# Asistente_Alzhaimer.net
KiCad netlist of a schematic drawn in EAGLE
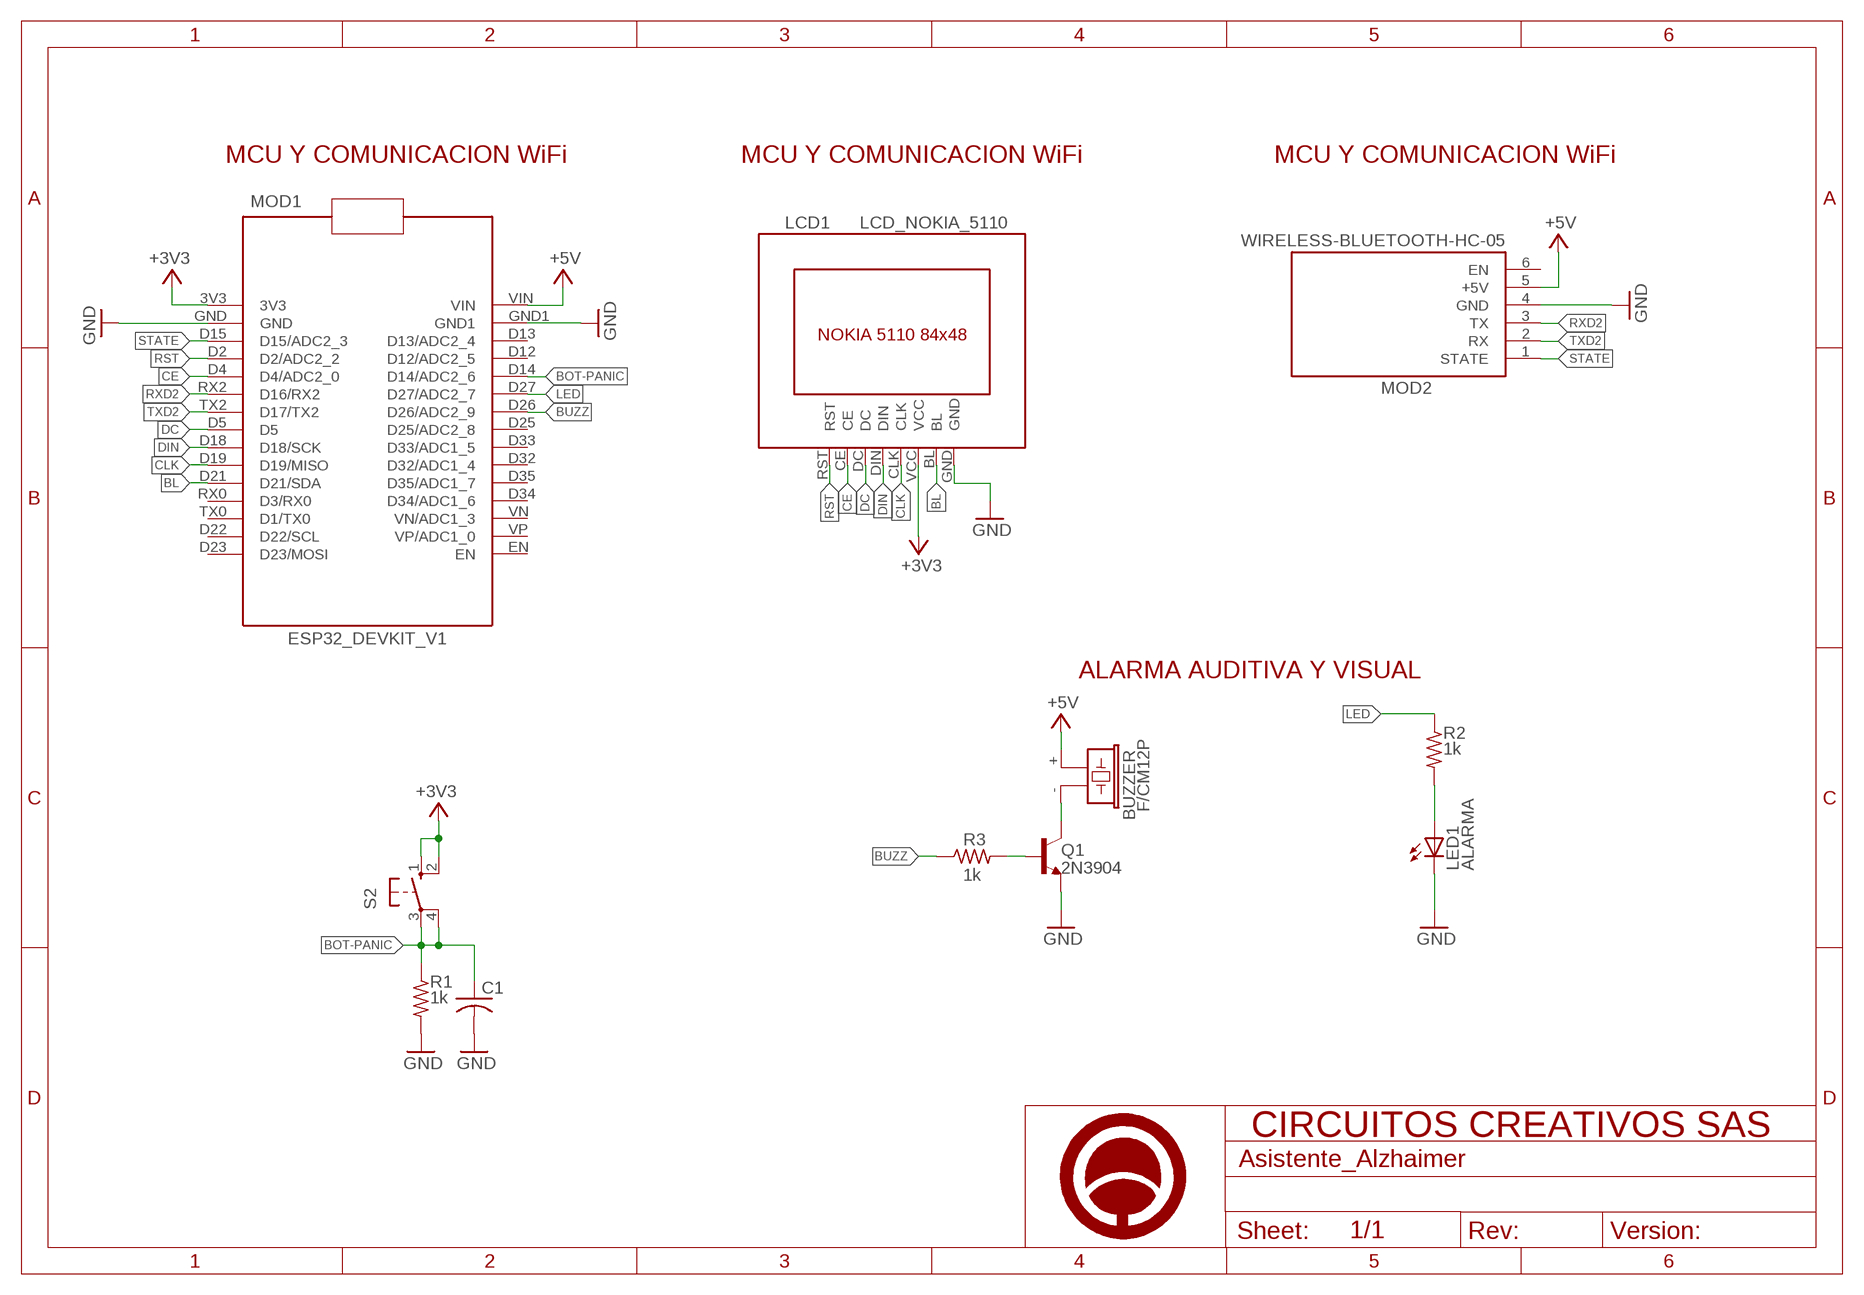
[diagram p0: schematic, sheet 1]

(export (version "E")
  (design (tool "Eeschema 10.0.6"))
  (components
    (comp (ref "BUZZER")
      (value "F/CM12P")
      (footprint "eagle-import:F_CM12P")
      (libsource (lib "eagle-import") (part "F/CM12P"))
    )
    (comp (ref "C1")
      (value "C-US050-025X075")
      (footprint "eagle-import:C050-025X075")
      (libsource (lib "eagle-import") (part "C-US050-025X075"))
    )
    (comp (ref "LCD1")
      (value "LCD_NOKIA_5110")
      (footprint "eagle-import:NOKIA_5110_THT")
      (libsource (lib "eagle-import") (part "LCD_NOKIA_5110"))
    )
    (comp (ref "LED1")
      (value "ALARMA")
      (footprint "eagle-import:LED3MM")
      (libsource (lib "eagle-import") (part "LED3MM"))
    )
    (comp (ref "MOD1")
      (value "ESP32_DEVKIT_V1")
      (footprint "eagle-import:ESP32_DEVKIT_V1")
      (libsource (lib "eagle-import") (part "ESP32_DEVKIT_V1"))
    )
    (comp (ref "MOD2")
      (value "WIRELESS-BLUETOOTH-HC-05")
      (footprint "eagle-import:WIRELESS-BLUETOOTH-HC-05")
      (libsource (lib "eagle-import") (part "WIRELESS-BLUETOOTH-HC-05"))
    )
    (comp (ref "Q1")
      (value "2N3904")
      (footprint "eagle-import:TO-92")
      (libsource (lib "eagle-import") (part "2N3904"))
    )
    (comp (ref "R1")
      (value "1k")
      (footprint "eagle-import:0204_7")
      (libsource (lib "eagle-import") (part "R-US_0204/7"))
    )
    (comp (ref "R2")
      (value "1k")
      (footprint "eagle-import:0204_7")
      (libsource (lib "eagle-import") (part "R-US_0204/7"))
    )
    (comp (ref "R3")
      (value "1k")
      (footprint "eagle-import:0204_7")
      (libsource (lib "eagle-import") (part "R-US_0204/7"))
    )
    (comp (ref "S2")
      (value "10-XX")
      (footprint "eagle-import:B3F-10XX")
      (fields (field (name "MPN") "B3F-1000"))
      (libsource (lib "eagle-import") (part "10-XX"))
    )
    (comp (ref "U$1")
      (value "A4_HORIZONTAL")
      (footprint "eagle-import:LOGO")
      (libsource (lib "eagle-import") (part "A4_HORIZONTAL"))
    )
  )
  (nets
    (net (code "1") (name "+3V3") (class "Default")
      (node (ref "LCD1") (pin "VCC") (pinfunction "VCC_VCC") (pintype "power_in"))
      (node (ref "MOD1") (pin "3V3") (pinfunction "3V3_3V3") (pintype "power_in"))
      (node (ref "S2") (pin "1") (pinfunction "S_1") (pintype "passive"))
      (node (ref "S2") (pin "2") (pinfunction "S1_2") (pintype "passive"))
    )
    (net (code "2") (name "+5V") (class "Default")
      (node (ref "BUZZER") (pin "+") (pinfunction "1_+") (pintype "passive"))
      (node (ref "MOD1") (pin "VIN") (pinfunction "VIN_VIN") (pintype "power_in"))
      (node (ref "MOD2") (pin "5") (pinfunction "+5V_5") (pintype "power_in"))
    )
    (net (code "3") (name "BL") (class "Default")
      (node (ref "LCD1") (pin "BL") (pinfunction "BL_BL") (pintype "bidirectional"))
      (node (ref "MOD1") (pin "D21") (pinfunction "D21/SDA_D21") (pintype "bidirectional"))
    )
    (net (code "4") (name "BOT-PANIC") (class "Default")
      (node (ref "C1") (pin "1") (pinfunction "1_1") (pintype "passive"))
      (node (ref "MOD1") (pin "D14") (pinfunction "D14/ADC2_6_D14") (pintype "bidirectional"))
      (node (ref "R1") (pin "1") (pinfunction "1_1") (pintype "passive"))
      (node (ref "S2") (pin "3") (pinfunction "P_3") (pintype "passive"))
      (node (ref "S2") (pin "4") (pinfunction "P1_4") (pintype "passive"))
    )
    (net (code "5") (name "BUZZ") (class "Default")
      (node (ref "MOD1") (pin "D26") (pinfunction "D26/ADC2_9_D26") (pintype "bidirectional"))
      (node (ref "R3") (pin "1") (pinfunction "1_1") (pintype "passive"))
    )
    (net (code "6") (name "CE") (class "Default")
      (node (ref "LCD1") (pin "CE") (pinfunction "CE_CE") (pintype "bidirectional"))
      (node (ref "MOD1") (pin "D4") (pinfunction "D4/ADC2_0_D4") (pintype "bidirectional"))
    )
    (net (code "7") (name "CLK") (class "Default")
      (node (ref "LCD1") (pin "CLK") (pinfunction "CLK_CLK") (pintype "bidirectional"))
      (node (ref "MOD1") (pin "D19") (pinfunction "D19/MISO_D19") (pintype "bidirectional"))
    )
    (net (code "8") (name "DC") (class "Default")
      (node (ref "LCD1") (pin "DC") (pinfunction "DC_DC") (pintype "bidirectional"))
      (node (ref "MOD1") (pin "D5") (pinfunction "D5_D5") (pintype "bidirectional"))
    )
    (net (code "9") (name "DIN") (class "Default")
      (node (ref "LCD1") (pin "DIN") (pinfunction "DIN_DIN") (pintype "bidirectional"))
      (node (ref "MOD1") (pin "D18") (pinfunction "D18/SCK_D18") (pintype "bidirectional"))
    )
    (net (code "10") (name "GND") (class "Default")
      (node (ref "C1") (pin "2") (pinfunction "2_2") (pintype "passive"))
      (node (ref "LCD1") (pin "GND") (pinfunction "GND_GND") (pintype "power_in"))
      (node (ref "LED1") (pin "K") (pinfunction "C_K") (pintype "passive"))
      (node (ref "MOD1") (pin "GND") (pinfunction "GND_GND") (pintype "power_in"))
      (node (ref "MOD1") (pin "GND1") (pinfunction "GND1_GND1") (pintype "power_in"))
      (node (ref "MOD2") (pin "4") (pinfunction "GND_4") (pintype "power_in"))
      (node (ref "Q1") (pin "1") (pinfunction "E_1") (pintype "passive"))
      (node (ref "R1") (pin "2") (pinfunction "2_2") (pintype "passive"))
    )
    (net (code "11") (name "LED") (class "Default")
      (node (ref "MOD1") (pin "D27") (pinfunction "D27/ADC2_7_D27") (pintype "bidirectional"))
      (node (ref "R2") (pin "1") (pinfunction "1_1") (pintype "passive"))
    )
    (net (code "12") (name "Net-(BUZZER-2)") (class "Default")
      (node (ref "BUZZER") (pin "-") (pinfunction "2_-") (pintype "passive"))
      (node (ref "Q1") (pin "3") (pinfunction "C_3") (pintype "passive"))
    )
    (net (code "13") (name "Net-(LED1-PadA)") (class "Default")
      (node (ref "LED1") (pin "A") (pinfunction "A_A") (pintype "passive"))
      (node (ref "R2") (pin "2") (pinfunction "2_2") (pintype "passive"))
    )
    (net (code "14") (name "Net-(Q1-B)") (class "Default")
      (node (ref "Q1") (pin "2") (pinfunction "B_2") (pintype "passive"))
      (node (ref "R3") (pin "2") (pinfunction "2_2") (pintype "passive"))
    )
    (net (code "15") (name "RST") (class "Default")
      (node (ref "LCD1") (pin "RST") (pinfunction "RST_RST") (pintype "bidirectional"))
      (node (ref "MOD1") (pin "D2") (pinfunction "D2/ADC2_2_D2") (pintype "bidirectional"))
    )
    (net (code "16") (name "RXD2") (class "Default")
      (node (ref "MOD1") (pin "RX2") (pinfunction "D16/RX2_RX2") (pintype "bidirectional"))
      (node (ref "MOD2") (pin "3") (pinfunction "TX_3") (pintype "bidirectional"))
    )
    (net (code "17") (name "STATE") (class "Default")
      (node (ref "MOD1") (pin "D15") (pinfunction "D15/ADC2_3_D15") (pintype "bidirectional"))
      (node (ref "MOD2") (pin "1") (pinfunction "STATE_1") (pintype "bidirectional"))
    )
    (net (code "18") (name "TXD2") (class "Default")
      (node (ref "MOD1") (pin "TX2") (pinfunction "D17/TX2_TX2") (pintype "bidirectional"))
      (node (ref "MOD2") (pin "2") (pinfunction "RX_2") (pintype "bidirectional"))
    )
    (net (code "19") (name "unconnected-(MOD1-D1{slash}TX0-PadTX0)") (class "Default")
      (node (ref "MOD1") (pin "TX0") (pinfunction "D1/TX0_TX0") (pintype "bidirectional"))
    )
    (net (code "20") (name "unconnected-(MOD1-D3{slash}RX0-PadRX0)") (class "Default")
      (node (ref "MOD1") (pin "RX0") (pinfunction "D3/RX0_RX0") (pintype "bidirectional"))
    )
    (net (code "21") (name "unconnected-(MOD1-D12{slash}ADC2_5-PadD12)") (class "Default")
      (node (ref "MOD1") (pin "D12") (pinfunction "D12/ADC2_5_D12") (pintype "bidirectional"))
    )
    (net (code "22") (name "unconnected-(MOD1-D13{slash}ADC2_4-PadD13)") (class "Default")
      (node (ref "MOD1") (pin "D13") (pinfunction "D13/ADC2_4_D13") (pintype "bidirectional"))
    )
    (net (code "23") (name "unconnected-(MOD1-D22{slash}SCL-PadD22)") (class "Default")
      (node (ref "MOD1") (pin "D22") (pinfunction "D22/SCL_D22") (pintype "bidirectional"))
    )
    (net (code "24") (name "unconnected-(MOD1-D23{slash}MOSI-PadD23)") (class "Default")
      (node (ref "MOD1") (pin "D23") (pinfunction "D23/MOSI_D23") (pintype "bidirectional"))
    )
    (net (code "25") (name "unconnected-(MOD1-D25{slash}ADC2_8-PadD25)") (class "Default")
      (node (ref "MOD1") (pin "D25") (pinfunction "D25/ADC2_8_D25") (pintype "bidirectional"))
    )
    (net (code "26") (name "unconnected-(MOD1-D32{slash}ADC1_4-PadD32)") (class "Default")
      (node (ref "MOD1") (pin "D32") (pinfunction "D32/ADC1_4_D32") (pintype "bidirectional"))
    )
    (net (code "27") (name "unconnected-(MOD1-D33{slash}ADC1_5-PadD33)") (class "Default")
      (node (ref "MOD1") (pin "D33") (pinfunction "D33/ADC1_5_D33") (pintype "bidirectional"))
    )
    (net (code "28") (name "unconnected-(MOD1-D34{slash}ADC1_6-PadD34)") (class "Default")
      (node (ref "MOD1") (pin "D34") (pinfunction "D34/ADC1_6_D34") (pintype "bidirectional"))
    )
    (net (code "29") (name "unconnected-(MOD1-D35{slash}ADC1_7-PadD35)") (class "Default")
      (node (ref "MOD1") (pin "D35") (pinfunction "D35/ADC1_7_D35") (pintype "bidirectional"))
    )
    (net (code "30") (name "unconnected-(MOD1-PadEN)") (class "Default")
      (node (ref "MOD1") (pin "EN") (pinfunction "EN_EN") (pintype "bidirectional"))
    )
    (net (code "31") (name "unconnected-(MOD1-VN{slash}ADC1_3-PadVN)") (class "Default")
      (node (ref "MOD1") (pin "VN") (pinfunction "VN/ADC1_3_VN") (pintype "bidirectional"))
    )
    (net (code "32") (name "unconnected-(MOD1-VP{slash}ADC1_0-PadVP)") (class "Default")
      (node (ref "MOD1") (pin "VP") (pinfunction "VP/ADC1_0_VP") (pintype "bidirectional"))
    )
    (net (code "33") (name "unconnected-(MOD2-EN-Pad6)") (class "Default")
      (node (ref "MOD2") (pin "6") (pinfunction "EN_6") (pintype "bidirectional"))
    )
  )
)
